# 3clamp_pulse_conv.net
KiCad netlist of a schematic drawn in EAGLE
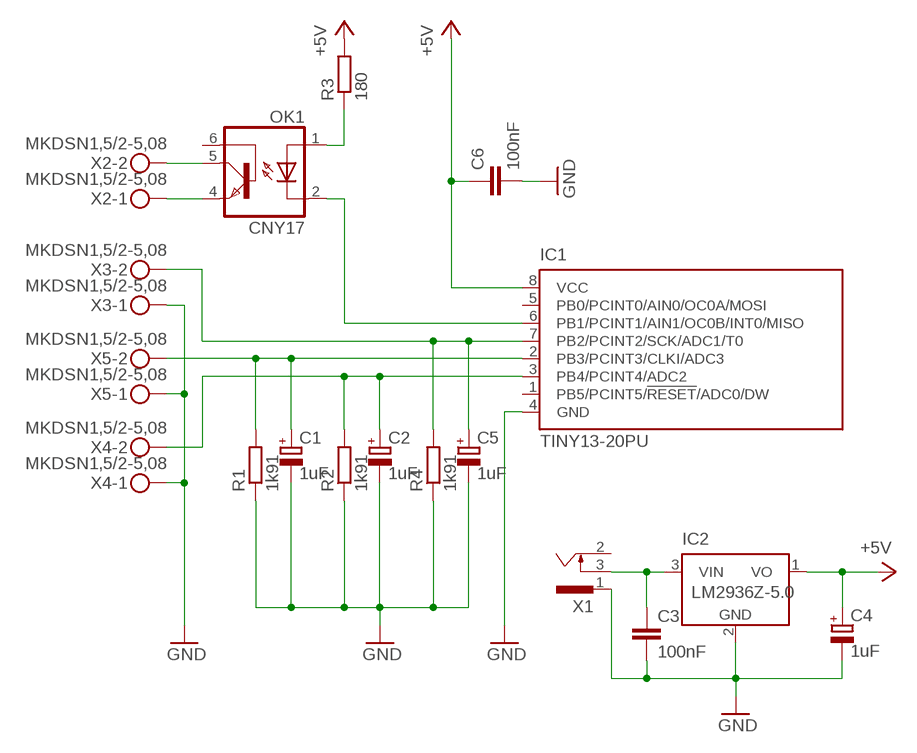
[diagram p0: schematic, sheet 1]

(export (version "E")
  (design (tool "Eeschema 10.0.6"))
  (components
    (comp (ref "C1")
      (value "1uF")
      (footprint "eagle-import:E2,5-5")
      (libsource (lib "eagle-import") (part "CPOL-EUE2.5-5"))
    )
    (comp (ref "C2")
      (value "1uF")
      (footprint "eagle-import:E2,5-5")
      (libsource (lib "eagle-import") (part "CPOL-EUE2.5-5"))
    )
    (comp (ref "C3")
      (value "100nF")
      (footprint "eagle-import:C025-025X050")
      (libsource (lib "eagle-import") (part "C-EU025-025X050"))
    )
    (comp (ref "C4")
      (value "1uF")
      (footprint "eagle-import:E2,5-5")
      (libsource (lib "eagle-import") (part "CPOL-EUE2.5-5"))
    )
    (comp (ref "C5")
      (value "1uF")
      (footprint "eagle-import:E2,5-5")
      (libsource (lib "eagle-import") (part "CPOL-EUE2.5-5"))
    )
    (comp (ref "C6")
      (value "100nF")
      (footprint "eagle-import:C025-025X050")
      (libsource (lib "eagle-import") (part "C-EU025-025X050"))
    )
    (comp (ref "IC1")
      (value "TINY13-20PU")
      (footprint "eagle-import:DIL08")
      (fields (field (name "MPN") "ATTINY13-20PU"))
      (libsource (lib "eagle-import") (part "TINY13PU-20"))
    )
    (comp (ref "IC2")
      (value "LM2936Z-5.0")
      (footprint "eagle-import:TO92")
      (fields (field (name "MF") "NATIONAL SEMICONDUCTOR") (field (name "MPN") "LM2936Z-5.0/NOPB"))
      (libsource (lib "eagle-import") (part "LM2936?Z-5.0"))
    )
    (comp (ref "OK1")
      (value "CNY17")
      (footprint "eagle-import:DIL06")
      (fields (field (name "MPN") "CNY17-1"))
      (libsource (lib "eagle-import") (part "CNY17"))
    )
    (comp (ref "R1")
      (value "1k91")
      (footprint "eagle-import:0204_7")
      (libsource (lib "eagle-import") (part "R-EU_0204/7"))
    )
    (comp (ref "R2")
      (value "1k91")
      (footprint "eagle-import:0204_7")
      (libsource (lib "eagle-import") (part "R-EU_0204/7"))
    )
    (comp (ref "R3")
      (value "180")
      (footprint "eagle-import:0204_7")
      (libsource (lib "eagle-import") (part "R-EU_0204/7"))
    )
    (comp (ref "R4")
      (value "1k91")
      (footprint "eagle-import:0204_7")
      (libsource (lib "eagle-import") (part "R-EU_0204/7"))
    )
    (comp (ref "X1")
      (value "SCD-014A")
      (footprint "eagle-import:SCD-014-A")
      (libsource (lib "eagle-import") (part "SCD-014A"))
    )
    (comp (ref "X2")
      (value "MKDSN1,5/2-5,08")
      (footprint "eagle-import:MKDSN1,5_2-5,08")
      (fields (field (name "MPN") "MKDSN 1,5/2-5.08"))
      (libsource (lib "eagle-import") (part "MKDSN1,5/2-5,08"))
    )
    (comp (ref "X3")
      (value "MKDSN1,5/2-5,08")
      (footprint "eagle-import:MKDSN1,5_2-5,08")
      (fields (field (name "MPN") "MKDSN 1,5/2-5.08"))
      (libsource (lib "eagle-import") (part "MKDSN1,5/2-5,08"))
    )
    (comp (ref "X4")
      (value "MKDSN1,5/2-5,08")
      (footprint "eagle-import:MKDSN1,5_2-5,08")
      (fields (field (name "MPN") "MKDSN 1,5/2-5.08"))
      (libsource (lib "eagle-import") (part "MKDSN1,5/2-5,08"))
    )
    (comp (ref "X5")
      (value "MKDSN1,5/2-5,08")
      (footprint "eagle-import:MKDSN1,5_2-5,08")
      (fields (field (name "MPN") "MKDSN 1,5/2-5.08"))
      (libsource (lib "eagle-import") (part "MKDSN1,5/2-5,08"))
    )
  )
  (nets
    (net (code "1") (name "+5V") (class "Default")
      (node (ref "C4") (pin "+") (pinfunction "+_+") (pintype "passive"))
      (node (ref "C6") (pin "1") (pinfunction "1_1") (pintype "passive"))
      (node (ref "IC1") (pin "8") (pinfunction "VCC_8") (pintype "power_in"))
      (node (ref "IC2") (pin "1") (pinfunction "VO_1") (pintype "passive"))
      (node (ref "R3") (pin "2") (pinfunction "2_2") (pintype "passive"))
    )
    (net (code "2") (name "GND") (class "Default")
      (node (ref "C1") (pin "-") (pinfunction "-_-") (pintype "passive"))
      (node (ref "C2") (pin "-") (pinfunction "-_-") (pintype "passive"))
      (node (ref "C3") (pin "2") (pinfunction "2_2") (pintype "passive"))
      (node (ref "C4") (pin "-") (pinfunction "-_-") (pintype "passive"))
      (node (ref "C5") (pin "-") (pinfunction "-_-") (pintype "passive"))
      (node (ref "C6") (pin "2") (pinfunction "2_2") (pintype "passive"))
      (node (ref "IC1") (pin "4") (pinfunction "GND_4") (pintype "power_in"))
      (node (ref "IC2") (pin "2") (pinfunction "GND_2") (pintype "passive"))
      (node (ref "R1") (pin "1") (pinfunction "1_1") (pintype "passive"))
      (node (ref "R2") (pin "1") (pinfunction "1_1") (pintype "passive"))
      (node (ref "R4") (pin "1") (pinfunction "1_1") (pintype "passive"))
      (node (ref "X1") (pin "1") (pinfunction "1_1") (pintype "passive"))
      (node (ref "X3") (pin "1") (pinfunction "KL_1") (pintype "passive"))
      (node (ref "X4") (pin "1") (pinfunction "KL_1") (pintype "passive"))
      (node (ref "X5") (pin "1") (pinfunction "KL_1") (pintype "passive"))
    )
    (net (code "3") (name "Net-(IC1-PB1{slash}PCINT1{slash}AIN1{slash}OC0B{slash}INT0{slash}MISO)") (class "Default")
      (node (ref "IC1") (pin "6") (pinfunction "PB1/PCINT1/AIN1/OC0B/INT0/MISO_6") (pintype "bidirectional"))
      (node (ref "OK1") (pin "2") (pinfunction "C_2") (pintype "passive"))
    )
    (net (code "4") (name "Net-(IC1-PB2{slash}PCINT2{slash}SCK{slash}ADC1{slash}T0)") (class "Default")
      (node (ref "C5") (pin "+") (pinfunction "+_+") (pintype "passive"))
      (node (ref "IC1") (pin "7") (pinfunction "PB2/PCINT2/SCK/ADC1/T0_7") (pintype "bidirectional"))
      (node (ref "R4") (pin "2") (pinfunction "2_2") (pintype "passive"))
      (node (ref "X3") (pin "2") (pinfunction "KL_2") (pintype "passive"))
    )
    (net (code "5") (name "Net-(IC1-PB3{slash}PCINT3{slash}CLKI{slash}ADC3)") (class "Default")
      (node (ref "C1") (pin "+") (pinfunction "+_+") (pintype "passive"))
      (node (ref "IC1") (pin "2") (pinfunction "PB3/PCINT3/CLKI/ADC3_2") (pintype "bidirectional"))
      (node (ref "R1") (pin "2") (pinfunction "2_2") (pintype "passive"))
      (node (ref "X5") (pin "2") (pinfunction "KL_2") (pintype "passive"))
    )
    (net (code "6") (name "Net-(IC1-PB4{slash}PCINT4{slash}ADC2)") (class "Default")
      (node (ref "C2") (pin "+") (pinfunction "+_+") (pintype "passive"))
      (node (ref "IC1") (pin "3") (pinfunction "PB4/PCINT4/ADC2_3") (pintype "bidirectional"))
      (node (ref "R2") (pin "2") (pinfunction "2_2") (pintype "passive"))
      (node (ref "X4") (pin "2") (pinfunction "KL_2") (pintype "passive"))
    )
    (net (code "7") (name "Net-(IC2-VIN)") (class "Default")
      (node (ref "C3") (pin "1") (pinfunction "1_1") (pintype "passive"))
      (node (ref "IC2") (pin "3") (pinfunction "VIN_3") (pintype "input"))
      (node (ref "X1") (pin "3") (pinfunction "3_3") (pintype "passive"))
    )
    (net (code "8") (name "Net-(OK1-A)") (class "Default")
      (node (ref "OK1") (pin "1") (pinfunction "A_1") (pintype "passive"))
      (node (ref "R3") (pin "1") (pinfunction "1_1") (pintype "passive"))
    )
    (net (code "9") (name "Net-(OK1-COL)") (class "Default")
      (node (ref "OK1") (pin "5") (pinfunction "COL_5") (pintype "passive"))
      (node (ref "X2") (pin "2") (pinfunction "KL_2") (pintype "passive"))
    )
    (net (code "10") (name "Net-(OK1-EMI)") (class "Default")
      (node (ref "OK1") (pin "4") (pinfunction "EMI_4") (pintype "passive"))
      (node (ref "X2") (pin "1") (pinfunction "KL_1") (pintype "passive"))
    )
    (net (code "11") (name "unconnected-(IC1-PB0{slash}PCINT0{slash}AIN0{slash}OC0A{slash}MOSI-Pad5)") (class "Default")
      (node (ref "IC1") (pin "5") (pinfunction "PB0/PCINT0/AIN0/OC0A/MOSI_5") (pintype "bidirectional"))
    )
    (net (code "12") (name "unconnected-(IC1-PB5{slash}PCINT5{slash}~{RESET}{slash}ADC0{slash}DW-Pad1)") (class "Default")
      (node (ref "IC1") (pin "1") (pinfunction "PB5/PCINT5/~{RESET}/ADC0/DW_1") (pintype "bidirectional"))
    )
    (net (code "13") (name "unconnected-(OK1-BAS-Pad6)") (class "Default")
      (node (ref "OK1") (pin "6") (pinfunction "BAS_6") (pintype "passive"))
    )
    (net (code "14") (name "unconnected-(X1-Pad2)") (class "Default")
      (node (ref "X1") (pin "2") (pinfunction "2_2") (pintype "passive"))
    )
  )
)
